# tcxo_breakout.net
KiCad netlist of a schematic drawn in EAGLE
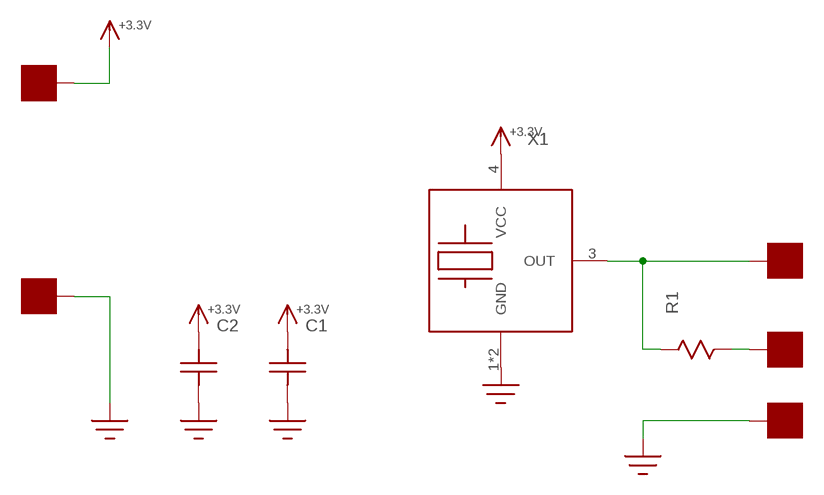
[diagram p0: schematic, sheet 1]

(export (version "E")
  (design (tool "Eeschema 10.0.6"))
  (components
    (comp (ref "C1")
      (value "C0603")
      (footprint "eagle-import:C0603")
      (libsource (lib "eagle-import") (part "C0603"))
    )
    (comp (ref "C2")
      (value "C0805")
      (footprint "eagle-import:0805")
      (libsource (lib "eagle-import") (part "C0805"))
    )
    (comp (ref "R1")
      (value "R0603")
      (footprint "eagle-import:R0603")
      (libsource (lib "eagle-import") (part "R0603"))
    )
    (comp (ref "U$1")
      (value "PAD100MIL")
      (footprint "eagle-import:PAD_100MIL")
      (libsource (lib "eagle-import") (part "PAD100MIL"))
    )
    (comp (ref "U$2")
      (value "PAD100MIL")
      (footprint "eagle-import:PAD_100MIL")
      (libsource (lib "eagle-import") (part "PAD100MIL"))
    )
    (comp (ref "U$3")
      (value "PAD100MIL")
      (footprint "eagle-import:PAD_100MIL")
      (libsource (lib "eagle-import") (part "PAD100MIL"))
    )
    (comp (ref "U$12")
      (value "PAD100MIL")
      (footprint "eagle-import:PAD_100MIL")
      (libsource (lib "eagle-import") (part "PAD100MIL"))
    )
    (comp (ref "U$13")
      (value "PAD100MIL")
      (footprint "eagle-import:PAD_100MIL")
      (libsource (lib "eagle-import") (part "PAD100MIL"))
    )
    (comp (ref "X1")
      (value "XTAL_OSC3.2X2.5")
      (footprint "eagle-import:XTAL_3.2X2.5")
      (libsource (lib "eagle-import") (part "XTAL_OSC3.2X2.5"))
    )
  )
  (nets
    (net (code "1") (name "+3.3V") (class "Default")
      (node (ref "C1") (pin "P$2") (pinfunction "P$2_P$2") (pintype "bidirectional"))
      (node (ref "C2") (pin "P$2") (pinfunction "P$2_P$2") (pintype "bidirectional"))
      (node (ref "U$1") (pin "P$1") (pinfunction "P$1_P$1") (pintype "bidirectional"))
      (node (ref "X1") (pin "4") (pinfunction "VCC_4") (pintype "bidirectional"))
    )
    (net (code "2") (name "GND") (class "Default")
      (node (ref "C1") (pin "P$1") (pinfunction "P$1_P$1") (pintype "bidirectional"))
      (node (ref "C2") (pin "P$1") (pinfunction "P$1_P$1") (pintype "bidirectional"))
      (node (ref "U$13") (pin "P$1") (pinfunction "P$1_P$1") (pintype "bidirectional"))
      (node (ref "U$2") (pin "P$1") (pinfunction "P$1_P$1") (pintype "bidirectional"))
      (node (ref "X1") (pin "1") (pinfunction "GND_1") (pintype "bidirectional"))
      (node (ref "X1") (pin "2") (pinfunction "GND_2") (pintype "bidirectional"))
    )
    (net (code "3") (name "Net-(R1-P$3)") (class "Default")
      (node (ref "R1") (pin "P$1") (pinfunction "P$3_P$1") (pintype "bidirectional"))
      (node (ref "U$3") (pin "P$1") (pinfunction "P$1_P$1") (pintype "bidirectional"))
      (node (ref "X1") (pin "3") (pinfunction "OUT_3") (pintype "bidirectional"))
    )
    (net (code "4") (name "Net-(R1-P$4)") (class "Default")
      (node (ref "R1") (pin "P$2") (pinfunction "P$4_P$2") (pintype "bidirectional"))
      (node (ref "U$12") (pin "P$1") (pinfunction "P$1_P$1") (pintype "bidirectional"))
    )
  )
)
